# rf24-isp.net
KiCad netlist of a schematic drawn in EAGLE
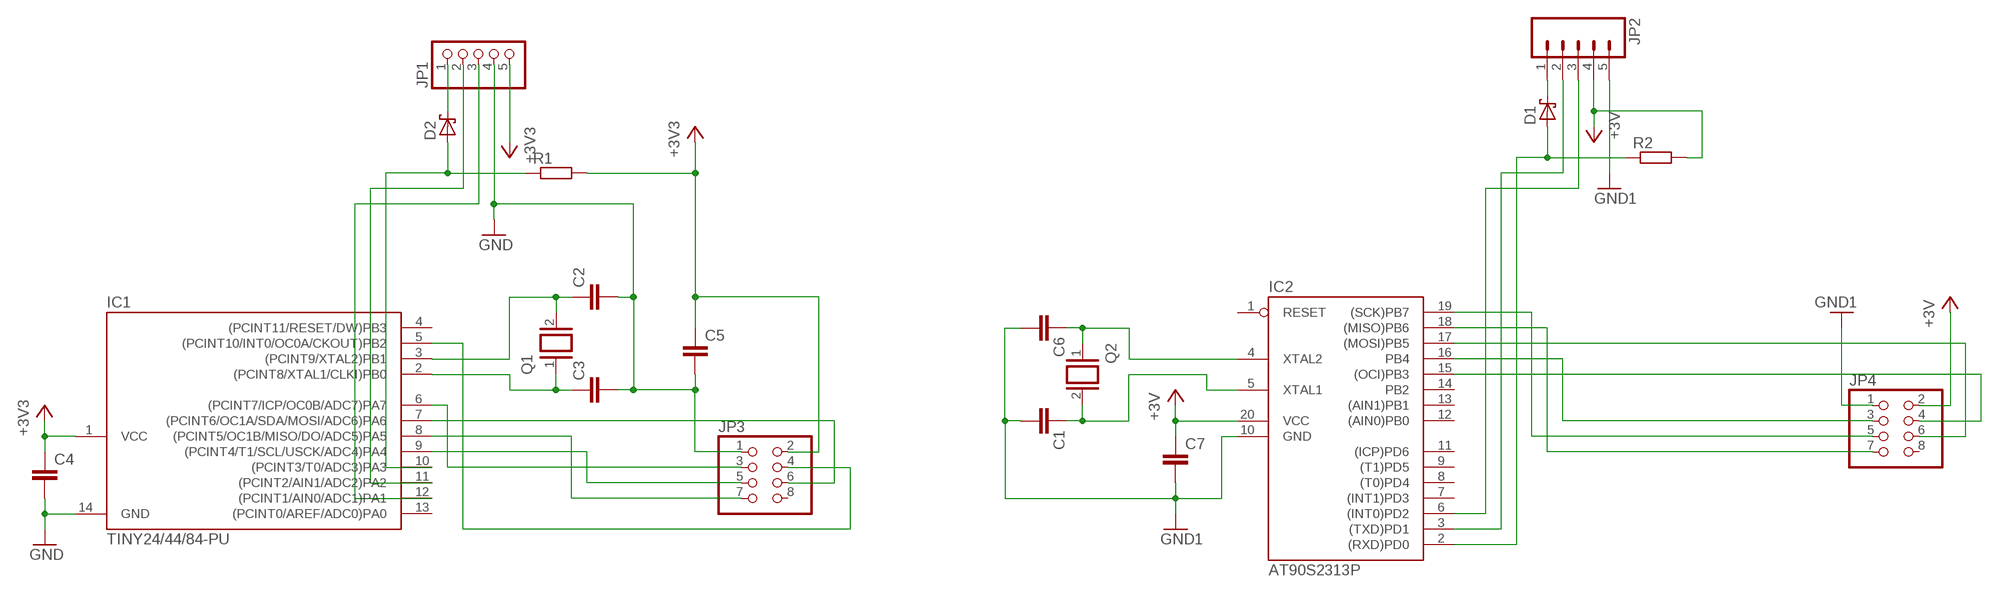
[diagram p0: schematic, sheet 1]

(export (version "E")
  (design (tool "Eeschema 10.0.6"))
  (components
    (comp (ref "C1")
      (value "C-EU025-025X050")
      (footprint "eagle-import:C025-025X050")
      (libsource (lib "eagle-import") (part "C-EU025-025X050"))
    )
    (comp (ref "C2")
      (value "C-EU025-025X050")
      (footprint "eagle-import:C025-025X050")
      (libsource (lib "eagle-import") (part "C-EU025-025X050"))
    )
    (comp (ref "C3")
      (value "C-EU025-025X050")
      (footprint "eagle-import:C025-025X050")
      (libsource (lib "eagle-import") (part "C-EU025-025X050"))
    )
    (comp (ref "C4")
      (value "C-EU025-025X050")
      (footprint "eagle-import:C025-025X050")
      (libsource (lib "eagle-import") (part "C-EU025-025X050"))
    )
    (comp (ref "C5")
      (value "C-EU025-025X050")
      (footprint "eagle-import:C025-025X050")
      (libsource (lib "eagle-import") (part "C-EU025-025X050"))
    )
    (comp (ref "C6")
      (value "C-EU025-025X050")
      (footprint "eagle-import:C025-025X050")
      (libsource (lib "eagle-import") (part "C-EU025-025X050"))
    )
    (comp (ref "C7")
      (value "C-EU025-025X050")
      (footprint "eagle-import:C025-025X050")
      (libsource (lib "eagle-import") (part "C-EU025-025X050"))
    )
    (comp (ref "D1")
      (value "SCHOTTKY-DIODETO92H")
      (footprint "eagle-import:TO92H")
      (libsource (lib "eagle-import") (part "SCHOTTKY-DIODETO92H"))
    )
    (comp (ref "D2")
      (value "SCHOTTKY-DIODETO92H")
      (footprint "eagle-import:TO92H")
      (libsource (lib "eagle-import") (part "SCHOTTKY-DIODETO92H"))
    )
    (comp (ref "IC1")
      (value "TINY24/44/84-PU")
      (footprint "eagle-import:DIL14")
      (libsource (lib "eagle-import") (part "TINY24/44/84-PU"))
    )
    (comp (ref "IC2")
      (value "AT90S2313P")
      (footprint "eagle-import:DIL20")
      (libsource (lib "eagle-import") (part "AT90S2313P"))
    )
    (comp (ref "JP1")
      (value "PINHD-1X5")
      (footprint "eagle-import:1X05")
      (libsource (lib "eagle-import") (part "PINHD-1X5"))
    )
    (comp (ref "JP2")
      (value "M05PTH")
      (footprint "eagle-import:1X05")
      (libsource (lib "eagle-import") (part "M05PTH"))
    )
    (comp (ref "JP3")
      (value "PINHD-2X4")
      (footprint "eagle-import:2X04")
      (libsource (lib "eagle-import") (part "PINHD-2X4"))
    )
    (comp (ref "JP4")
      (value "PINHD-2X4")
      (footprint "eagle-import:2X04")
      (libsource (lib "eagle-import") (part "PINHD-2X4"))
    )
    (comp (ref "Q1")
      (value "XTAL/S")
      (footprint "eagle-import:QS")
      (libsource (lib "eagle-import") (part "XTAL/S"))
    )
    (comp (ref "Q2")
      (value "XTAL/S")
      (footprint "eagle-import:QS")
      (libsource (lib "eagle-import") (part "XTAL/S"))
    )
    (comp (ref "R1")
      (value "R-EU_0207/12")
      (footprint "eagle-import:0207_12")
      (libsource (lib "eagle-import") (part "R-EU_0207/12"))
    )
    (comp (ref "R2")
      (value "R-EU_0207/2V")
      (footprint "eagle-import:0207_2V")
      (libsource (lib "eagle-import") (part "R-EU_0207/2V"))
    )
  )
  (nets
    (net (code "1") (name "+3V") (class "Default")
      (node (ref "C4") (pin "1") (pinfunction "1_1") (pintype "passive"))
      (node (ref "C5") (pin "1") (pinfunction "1_1") (pintype "passive"))
      (node (ref "C7") (pin "1") (pinfunction "1_1") (pintype "passive"))
      (node (ref "IC1") (pin "1") (pinfunction "VCC_1") (pintype "power_in"))
      (node (ref "IC2") (pin "20") (pinfunction "VCC_20") (pintype "power_in"))
      (node (ref "JP1") (pin "5") (pinfunction "5_5") (pintype "passive"))
      (node (ref "JP2") (pin "4") (pinfunction "4_4") (pintype "passive"))
      (node (ref "JP3") (pin "2") (pinfunction "2_2") (pintype "passive"))
      (node (ref "JP4") (pin "2") (pinfunction "2_2") (pintype "passive"))
      (node (ref "R1") (pin "2") (pinfunction "2_2") (pintype "passive"))
      (node (ref "R2") (pin "2") (pinfunction "2_2") (pintype "passive"))
    )
    (net (code "2") (name "GND") (class "Default")
      (node (ref "C1") (pin "2") (pinfunction "2_2") (pintype "passive"))
      (node (ref "C2") (pin "2") (pinfunction "2_2") (pintype "passive"))
      (node (ref "C3") (pin "2") (pinfunction "2_2") (pintype "passive"))
      (node (ref "C4") (pin "2") (pinfunction "2_2") (pintype "passive"))
      (node (ref "C5") (pin "2") (pinfunction "2_2") (pintype "passive"))
      (node (ref "C6") (pin "2") (pinfunction "2_2") (pintype "passive"))
      (node (ref "C7") (pin "2") (pinfunction "2_2") (pintype "passive"))
      (node (ref "IC1") (pin "14") (pinfunction "GND_14") (pintype "power_in"))
      (node (ref "IC2") (pin "10") (pinfunction "GND_10") (pintype "power_in"))
      (node (ref "JP1") (pin "4") (pinfunction "4_4") (pintype "passive"))
      (node (ref "JP2") (pin "5") (pinfunction "5_5") (pintype "passive"))
      (node (ref "JP3") (pin "1") (pinfunction "1_1") (pintype "passive"))
      (node (ref "JP4") (pin "1") (pinfunction "1_1") (pintype "passive"))
    )
    (net (code "3") (name "Net-(D1-A)") (class "Default")
      (node (ref "D1") (pin "1") (pinfunction "A_1") (pintype "passive"))
      (node (ref "IC2") (pin "2") (pinfunction "(RXD)PD0_2") (pintype "bidirectional"))
      (node (ref "R2") (pin "1") (pinfunction "1_1") (pintype "passive"))
    )
    (net (code "4") (name "Net-(D1-C)") (class "Default")
      (node (ref "D1") (pin "2") (pinfunction "C_2") (pintype "passive"))
      (node (ref "JP2") (pin "1") (pinfunction "1_1") (pintype "passive"))
    )
    (net (code "5") (name "Net-(D2-A)") (class "Default")
      (node (ref "D2") (pin "1") (pinfunction "A_1") (pintype "passive"))
      (node (ref "IC1") (pin "10") (pinfunction "(PCINT3/T0/ADC3)PA3_10") (pintype "bidirectional"))
      (node (ref "R1") (pin "1") (pinfunction "1_1") (pintype "passive"))
    )
    (net (code "6") (name "Net-(D2-C)") (class "Default")
      (node (ref "D2") (pin "2") (pinfunction "C_2") (pintype "passive"))
      (node (ref "JP1") (pin "1") (pinfunction "1_1") (pintype "passive"))
    )
    (net (code "7") (name "Net-(IC1-(PCINT1{slash}AIN0{slash}ADC1)PA1)") (class "Default")
      (node (ref "IC1") (pin "12") (pinfunction "(PCINT1/AIN0/ADC1)PA1_12") (pintype "bidirectional"))
      (node (ref "JP1") (pin "3") (pinfunction "3_3") (pintype "passive"))
    )
    (net (code "8") (name "Net-(IC1-(PCINT2{slash}AIN1{slash}ADC2)PA2)") (class "Default")
      (node (ref "IC1") (pin "11") (pinfunction "(PCINT2/AIN1/ADC2)PA2_11") (pintype "bidirectional"))
      (node (ref "JP1") (pin "2") (pinfunction "2_2") (pintype "passive"))
    )
    (net (code "9") (name "Net-(IC1-(PCINT4{slash}T1{slash}SCL{slash}USCK{slash}ADC4)PA4)") (class "Default")
      (node (ref "IC1") (pin "9") (pinfunction "(PCINT4/T1/SCL/USCK/ADC4)PA4_9") (pintype "bidirectional"))
      (node (ref "JP3") (pin "5") (pinfunction "5_5") (pintype "passive"))
    )
    (net (code "10") (name "Net-(IC1-(PCINT5{slash}OC1B{slash}MISO{slash}DO{slash}ADC5)PA5)") (class "Default")
      (node (ref "IC1") (pin "8") (pinfunction "(PCINT5/OC1B/MISO/DO/ADC5)PA5_8") (pintype "bidirectional"))
      (node (ref "JP3") (pin "7") (pinfunction "7_7") (pintype "passive"))
    )
    (net (code "11") (name "Net-(IC1-(PCINT6{slash}OC1A{slash}SDA{slash}MOSI{slash}ADC6)PA6)") (class "Default")
      (node (ref "IC1") (pin "7") (pinfunction "(PCINT6/OC1A/SDA/MOSI/ADC6)PA6_7") (pintype "bidirectional"))
      (node (ref "JP3") (pin "6") (pinfunction "6_6") (pintype "passive"))
    )
    (net (code "12") (name "Net-(IC1-(PCINT7{slash}ICP{slash}OC0B{slash}ADC7)PA7)") (class "Default")
      (node (ref "IC1") (pin "6") (pinfunction "(PCINT7/ICP/OC0B/ADC7)PA7_6") (pintype "bidirectional"))
      (node (ref "JP3") (pin "3") (pinfunction "3_3") (pintype "passive"))
    )
    (net (code "13") (name "Net-(IC1-(PCINT8{slash}XTAL1{slash}CLKI)PB0)") (class "Default")
      (node (ref "C3") (pin "1") (pinfunction "1_1") (pintype "passive"))
      (node (ref "IC1") (pin "2") (pinfunction "(PCINT8/XTAL1/CLKI)PB0_2") (pintype "bidirectional"))
      (node (ref "Q1") (pin "1") (pinfunction "1_1") (pintype "passive"))
    )
    (net (code "14") (name "Net-(IC1-(PCINT9{slash}XTAL2)PB1)") (class "Default")
      (node (ref "C2") (pin "1") (pinfunction "1_1") (pintype "passive"))
      (node (ref "IC1") (pin "3") (pinfunction "(PCINT9/XTAL2)PB1_3") (pintype "bidirectional"))
      (node (ref "Q1") (pin "2") (pinfunction "2_2") (pintype "passive"))
    )
    (net (code "15") (name "Net-(IC1-(PCINT10{slash}INT0{slash}OC0A{slash}CKOUT)PB2)") (class "Default")
      (node (ref "IC1") (pin "5") (pinfunction "(PCINT10/INT0/OC0A/CKOUT)PB2_5") (pintype "bidirectional"))
      (node (ref "JP3") (pin "4") (pinfunction "4_4") (pintype "passive"))
    )
    (net (code "16") (name "Net-(IC2-(INT0)PD2)") (class "Default")
      (node (ref "IC2") (pin "6") (pinfunction "(INT0)PD2_6") (pintype "bidirectional"))
      (node (ref "JP2") (pin "3") (pinfunction "3_3") (pintype "passive"))
    )
    (net (code "17") (name "Net-(IC2-(MISO)PB6)") (class "Default")
      (node (ref "IC2") (pin "18") (pinfunction "(MISO)PB6_18") (pintype "bidirectional"))
      (node (ref "JP4") (pin "7") (pinfunction "7_7") (pintype "passive"))
    )
    (net (code "18") (name "Net-(IC2-(MOSI)PB5)") (class "Default")
      (node (ref "IC2") (pin "17") (pinfunction "(MOSI)PB5_17") (pintype "bidirectional"))
      (node (ref "JP4") (pin "6") (pinfunction "6_6") (pintype "passive"))
    )
    (net (code "19") (name "Net-(IC2-(OCI)PB3)") (class "Default")
      (node (ref "IC2") (pin "15") (pinfunction "(OCI)PB3_15") (pintype "bidirectional"))
      (node (ref "JP4") (pin "4") (pinfunction "4_4") (pintype "passive"))
    )
    (net (code "20") (name "Net-(IC2-(SCK)PB7)") (class "Default")
      (node (ref "IC2") (pin "19") (pinfunction "(SCK)PB7_19") (pintype "bidirectional"))
      (node (ref "JP4") (pin "5") (pinfunction "5_5") (pintype "passive"))
    )
    (net (code "21") (name "Net-(IC2-(TXD)PD1)") (class "Default")
      (node (ref "IC2") (pin "3") (pinfunction "(TXD)PD1_3") (pintype "bidirectional"))
      (node (ref "JP2") (pin "2") (pinfunction "2_2") (pintype "passive"))
    )
    (net (code "22") (name "Net-(IC2-PB4)") (class "Default")
      (node (ref "IC2") (pin "16") (pinfunction "PB4_16") (pintype "bidirectional"))
      (node (ref "JP4") (pin "3") (pinfunction "3_3") (pintype "passive"))
    )
    (net (code "23") (name "Net-(IC2-XTAL1)") (class "Default")
      (node (ref "C1") (pin "1") (pinfunction "1_1") (pintype "passive"))
      (node (ref "IC2") (pin "5") (pinfunction "XTAL1_5") (pintype "bidirectional"))
      (node (ref "Q2") (pin "2") (pinfunction "2_2") (pintype "passive"))
    )
    (net (code "24") (name "Net-(IC2-XTAL2)") (class "Default")
      (node (ref "C6") (pin "1") (pinfunction "1_1") (pintype "passive"))
      (node (ref "IC2") (pin "4") (pinfunction "XTAL2_4") (pintype "bidirectional"))
      (node (ref "Q2") (pin "1") (pinfunction "1_1") (pintype "passive"))
    )
    (net (code "25") (name "unconnected-(IC1-(PCINT0{slash}AREF{slash}ADC0)PA0-Pad13)") (class "Default")
      (node (ref "IC1") (pin "13") (pinfunction "(PCINT0/AREF/ADC0)PA0_13") (pintype "bidirectional"))
    )
    (net (code "26") (name "unconnected-(IC1-(PCINT11{slash}RESET{slash}DW)PB3-Pad4)") (class "Default")
      (node (ref "IC1") (pin "4") (pinfunction "(PCINT11/RESET/DW)PB3_4") (pintype "bidirectional"))
    )
    (net (code "27") (name "unconnected-(IC2-(AIN0)PB0-Pad12)") (class "Default")
      (node (ref "IC2") (pin "12") (pinfunction "(AIN0)PB0_12") (pintype "bidirectional"))
    )
    (net (code "28") (name "unconnected-(IC2-(AIN1)PB1-Pad13)") (class "Default")
      (node (ref "IC2") (pin "13") (pinfunction "(AIN1)PB1_13") (pintype "bidirectional"))
    )
    (net (code "29") (name "unconnected-(IC2-(ICP)PD6-Pad11)") (class "Default")
      (node (ref "IC2") (pin "11") (pinfunction "(ICP)PD6_11") (pintype "bidirectional"))
    )
    (net (code "30") (name "unconnected-(IC2-(INT1)PD3-Pad7)") (class "Default")
      (node (ref "IC2") (pin "7") (pinfunction "(INT1)PD3_7") (pintype "bidirectional"))
    )
    (net (code "31") (name "unconnected-(IC2-(T0)PD4-Pad8)") (class "Default")
      (node (ref "IC2") (pin "8") (pinfunction "(T0)PD4_8") (pintype "bidirectional"))
    )
    (net (code "32") (name "unconnected-(IC2-(T1)PD5-Pad9)") (class "Default")
      (node (ref "IC2") (pin "9") (pinfunction "(T1)PD5_9") (pintype "bidirectional"))
    )
    (net (code "33") (name "unconnected-(IC2-PB2-Pad14)") (class "Default")
      (node (ref "IC2") (pin "14") (pinfunction "PB2_14") (pintype "bidirectional"))
    )
    (net (code "34") (name "unconnected-(IC2-RESET-Pad1)") (class "Default")
      (node (ref "IC2") (pin "1") (pinfunction "RESET_1") (pintype "bidirectional"))
    )
    (net (code "35") (name "unconnected-(JP3-Pad8)") (class "Default")
      (node (ref "JP3") (pin "8") (pinfunction "8_8") (pintype "passive"))
    )
    (net (code "36") (name "unconnected-(JP4-Pad8)") (class "Default")
      (node (ref "JP4") (pin "8") (pinfunction "8_8") (pintype "passive"))
    )
  )
)
